# infinity_mirror_revf.net
KiCad netlist of a schematic drawn in EAGLE
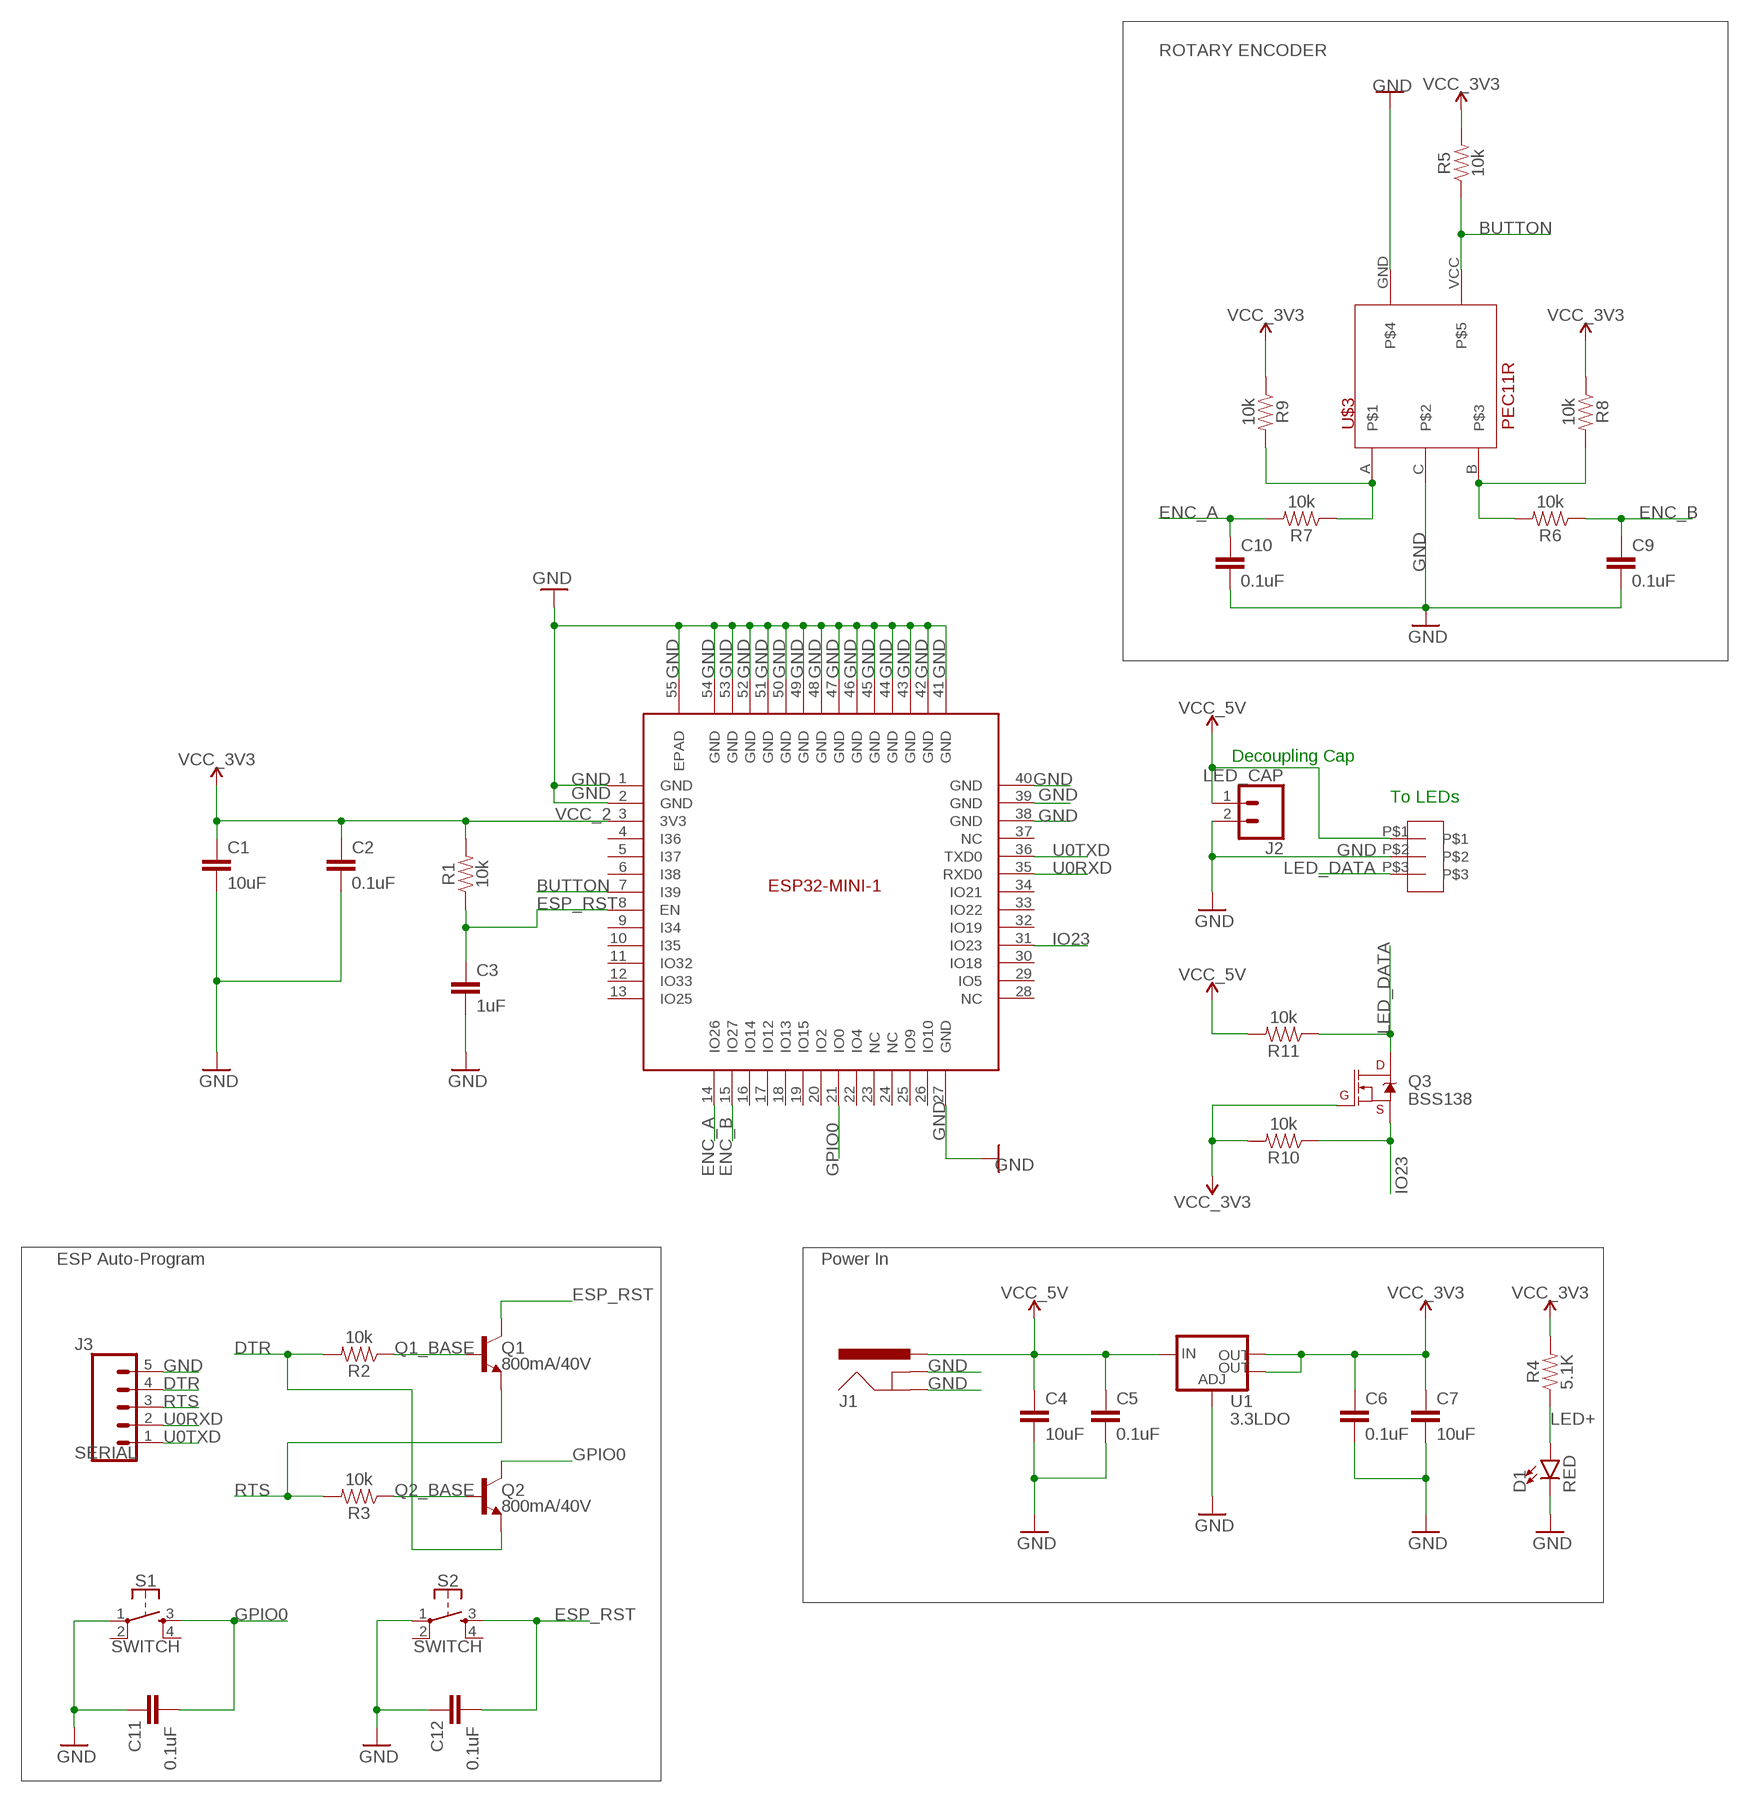
[diagram p0: schematic, sheet 1]

(export (version "E")
  (design (tool "Eeschema 10.0.6"))
  (components
    (comp (ref "C1")
      (value "10uF")
      (footprint "eagle-import:0805")
      (libsource (lib "eagle-import") (part "CAPACITOR"))
    )
    (comp (ref "C2")
      (value "0.1uF")
      (footprint "eagle-import:0805")
      (libsource (lib "eagle-import") (part "CAPACITOR"))
    )
    (comp (ref "C3")
      (value "1uF")
      (footprint "eagle-import:0805")
      (libsource (lib "eagle-import") (part "CAPACITOR"))
    )
    (comp (ref "C4")
      (value "10uF")
      (footprint "eagle-import:0805")
      (libsource (lib "eagle-import") (part "CAPACITOR"))
    )
    (comp (ref "C5")
      (value "0.1uF")
      (footprint "eagle-import:0805")
      (libsource (lib "eagle-import") (part "CAPACITOR"))
    )
    (comp (ref "C6")
      (value "0.1uF")
      (footprint "eagle-import:0805")
      (libsource (lib "eagle-import") (part "CAPACITOR"))
    )
    (comp (ref "C7")
      (value "10uF")
      (footprint "eagle-import:0805")
      (libsource (lib "eagle-import") (part "CAPACITOR"))
    )
    (comp (ref "C9")
      (value "0.1uF")
      (footprint "eagle-import:0805")
      (libsource (lib "eagle-import") (part "CAPACITOR"))
    )
    (comp (ref "C10")
      (value "0.1uF")
      (footprint "eagle-import:0805")
      (libsource (lib "eagle-import") (part "CAPACITOR"))
    )
    (comp (ref "C11")
      (value "0.1uF")
      (footprint "eagle-import:0805")
      (libsource (lib "eagle-import") (part "CAPACITOR"))
    )
    (comp (ref "C12")
      (value "0.1uF")
      (footprint "eagle-import:0805")
      (libsource (lib "eagle-import") (part "CAPACITOR"))
    )
    (comp (ref "D1")
      (value "RED")
      (footprint "eagle-import:LED-1206")
      (libsource (lib "eagle-import") (part "LED-RED1206"))
    )
    (comp (ref "J1")
      (value "POWER_JACKPTH_BREAD")
      (footprint "eagle-import:POWER_JACK_PTH_BREAD")
      (libsource (lib "eagle-import") (part "POWER_JACKPTH_BREAD"))
    )
    (comp (ref "J2")
      (value "LED_CAP")
      (footprint "eagle-import:1X02")
      (libsource (lib "eagle-import") (part "CONN_02"))
    )
    (comp (ref "J3")
      (value "SERIAL")
      (footprint "eagle-import:1X05")
      (libsource (lib "eagle-import") (part "CONN_05"))
    )
    (comp (ref "Q1")
      (value "800mA/40V")
      (footprint "eagle-import:SOT23-3")
      (libsource (lib "eagle-import") (part "TRANS_NPN-MMBT2222AL"))
    )
    (comp (ref "Q2")
      (value "800mA/40V")
      (footprint "eagle-import:SOT23-3")
      (libsource (lib "eagle-import") (part "TRANS_NPN-MMBT2222AL"))
    )
    (comp (ref "Q3")
      (value "BSS138")
      (footprint "eagle-import:SOT23-3")
      (libsource (lib "eagle-import") (part "MOSFET-NCH-BSS138"))
    )
    (comp (ref "R1")
      (value "10k")
      (footprint "eagle-import:0805")
      (libsource (lib "eagle-import") (part "RESISTOR"))
    )
    (comp (ref "R2")
      (value "10k")
      (footprint "eagle-import:0805")
      (libsource (lib "eagle-import") (part "RESISTOR"))
    )
    (comp (ref "R3")
      (value "10k")
      (footprint "eagle-import:0805")
      (libsource (lib "eagle-import") (part "RESISTOR"))
    )
    (comp (ref "R4")
      (value "5.1K")
      (footprint "eagle-import:0805")
      (libsource (lib "eagle-import") (part "RESISTOR"))
    )
    (comp (ref "R5")
      (value "10k")
      (footprint "eagle-import:0805")
      (libsource (lib "eagle-import") (part "RESISTOR"))
    )
    (comp (ref "R6")
      (value "10k")
      (footprint "eagle-import:0805")
      (libsource (lib "eagle-import") (part "RESISTOR"))
    )
    (comp (ref "R7")
      (value "10k")
      (footprint "eagle-import:0805")
      (libsource (lib "eagle-import") (part "RESISTOR"))
    )
    (comp (ref "R8")
      (value "10k")
      (footprint "eagle-import:0805")
      (libsource (lib "eagle-import") (part "RESISTOR"))
    )
    (comp (ref "R9")
      (value "10k")
      (footprint "eagle-import:0805")
      (libsource (lib "eagle-import") (part "RESISTOR"))
    )
    (comp (ref "R10")
      (value "10k")
      (footprint "eagle-import:0805")
      (libsource (lib "eagle-import") (part "RESISTOR"))
    )
    (comp (ref "R11")
      (value "10k")
      (footprint "eagle-import:0805")
      (libsource (lib "eagle-import") (part "RESISTOR"))
    )
    (comp (ref "S1")
      (value "SWITCH")
      (footprint "eagle-import:TACTILE_SWITCH_SMD_5.2MM")
      (libsource (lib "eagle-import") (part "MOMENTARY-SWITCH-SPST-2-SMD-5.2MM-TALL"))
    )
    (comp (ref "S2")
      (value "SWITCH")
      (footprint "eagle-import:TACTILE_SWITCH_SMD_5.2MM")
      (libsource (lib "eagle-import") (part "MOMENTARY-SWITCH-SPST-2-SMD-5.2MM-TALL"))
    )
    (comp (ref "U$1")
      (value "ESP32-MINI-1-N4")
      (footprint "eagle-import:ESP32-MINI-1-N4")
      (libsource (lib "eagle-import") (part "ESP32-MINI-1-N4"))
    )
    (comp (ref "U$2")
      (value "3-PIN-JST")
      (footprint "eagle-import:3-PIN-JST")
      (libsource (lib "eagle-import") (part "3-PIN-JST"))
    )
    (comp (ref "U$3")
      (value "PEC11R")
      (footprint "eagle-import:PEC11R-4320F-S0012")
      (libsource (lib "eagle-import") (part "PEC11R_ROTARY_ENCODER"))
    )
    (comp (ref "U1")
      (value "3.3LDO")
      (footprint "eagle-import:SOT223")
      (libsource (lib "eagle-import") (part "V_REG_LM1117SOT223"))
    )
  )
  (nets
    (net (code "1") (name "/BUTTON") (class "Default")
      (node (ref "R5") (pin "1") (pinfunction "1_1") (pintype "passive"))
      (node (ref "U$1") (pin "7") (pinfunction "I39_7") (pintype "bidirectional"))
      (node (ref "U$3") (pin "VCC") (pinfunction "P$5_VCC") (pintype "bidirectional"))
    )
    (net (code "2") (name "/DTR") (class "Default")
      (node (ref "J3") (pin "4") (pinfunction "4_4") (pintype "passive"))
      (node (ref "Q2") (pin "2") (pinfunction "E_2") (pintype "passive"))
      (node (ref "R2") (pin "2") (pinfunction "2_2") (pintype "passive"))
    )
    (net (code "3") (name "/ENC_A") (class "Default")
      (node (ref "C10") (pin "1") (pinfunction "1_1") (pintype "passive"))
      (node (ref "R7") (pin "2") (pinfunction "2_2") (pintype "passive"))
      (node (ref "U$1") (pin "14") (pinfunction "IO26_14") (pintype "bidirectional"))
    )
    (net (code "4") (name "/ENC_B") (class "Default")
      (node (ref "C9") (pin "1") (pinfunction "1_1") (pintype "passive"))
      (node (ref "R6") (pin "1") (pinfunction "1_1") (pintype "passive"))
      (node (ref "U$1") (pin "15") (pinfunction "IO27_15") (pintype "bidirectional"))
    )
    (net (code "5") (name "/ESP_RST") (class "Default")
      (node (ref "C12") (pin "2") (pinfunction "2_2") (pintype "passive"))
      (node (ref "C3") (pin "1") (pinfunction "1_1") (pintype "passive"))
      (node (ref "Q1") (pin "3") (pinfunction "C_3") (pintype "passive"))
      (node (ref "R1") (pin "1") (pinfunction "1_1") (pintype "passive"))
      (node (ref "S2") (pin "3") (pinfunction "3_3") (pintype "passive"))
      (node (ref "U$1") (pin "8") (pinfunction "EN_8") (pintype "bidirectional"))
    )
    (net (code "6") (name "/GPIO0") (class "Default")
      (node (ref "C11") (pin "2") (pinfunction "2_2") (pintype "passive"))
      (node (ref "Q2") (pin "3") (pinfunction "C_3") (pintype "passive"))
      (node (ref "S1") (pin "3") (pinfunction "3_3") (pintype "passive"))
      (node (ref "U$1") (pin "21") (pinfunction "IO0_21") (pintype "bidirectional"))
    )
    (net (code "7") (name "/IO23") (class "Default")
      (node (ref "Q3") (pin "2") (pinfunction "S_2") (pintype "bidirectional"))
      (node (ref "R10") (pin "1") (pinfunction "1_1") (pintype "passive"))
      (node (ref "U$1") (pin "31") (pinfunction "IO23_31") (pintype "bidirectional"))
    )
    (net (code "8") (name "/LED+") (class "Default")
      (node (ref "D1") (pin "A") (pinfunction "A_A") (pintype "passive"))
      (node (ref "R4") (pin "1") (pinfunction "1_1") (pintype "passive"))
    )
    (net (code "9") (name "/LED_DATA") (class "Default")
      (node (ref "Q3") (pin "3") (pinfunction "D_3") (pintype "bidirectional"))
      (node (ref "R11") (pin "1") (pinfunction "1_1") (pintype "passive"))
      (node (ref "U$2") (pin "P$3") (pinfunction "P$3_P$3") (pintype "bidirectional"))
    )
    (net (code "10") (name "/Q1_BASE") (class "Default")
      (node (ref "Q1") (pin "1") (pinfunction "B_1") (pintype "passive"))
      (node (ref "R2") (pin "1") (pinfunction "1_1") (pintype "passive"))
    )
    (net (code "11") (name "/Q2_BASE") (class "Default")
      (node (ref "Q2") (pin "1") (pinfunction "B_1") (pintype "passive"))
      (node (ref "R3") (pin "1") (pinfunction "1_1") (pintype "passive"))
    )
    (net (code "12") (name "/RTS") (class "Default")
      (node (ref "J3") (pin "3") (pinfunction "3_3") (pintype "passive"))
      (node (ref "Q1") (pin "2") (pinfunction "E_2") (pintype "passive"))
      (node (ref "R3") (pin "2") (pinfunction "2_2") (pintype "passive"))
    )
    (net (code "13") (name "/U0RXD") (class "Default")
      (node (ref "J3") (pin "2") (pinfunction "2_2") (pintype "passive"))
      (node (ref "U$1") (pin "35") (pinfunction "RXD0_35") (pintype "bidirectional"))
    )
    (net (code "14") (name "/U0TXD") (class "Default")
      (node (ref "J3") (pin "1") (pinfunction "1_1") (pintype "passive"))
      (node (ref "U$1") (pin "36") (pinfunction "TXD0_36") (pintype "bidirectional"))
    )
    (net (code "15") (name "GND") (class "Default")
      (node (ref "C1") (pin "2") (pinfunction "2_2") (pintype "passive"))
      (node (ref "C10") (pin "2") (pinfunction "2_2") (pintype "passive"))
      (node (ref "C11") (pin "1") (pinfunction "1_1") (pintype "passive"))
      (node (ref "C12") (pin "1") (pinfunction "1_1") (pintype "passive"))
      (node (ref "C2") (pin "2") (pinfunction "2_2") (pintype "passive"))
      (node (ref "C3") (pin "2") (pinfunction "2_2") (pintype "passive"))
      (node (ref "C4") (pin "2") (pinfunction "2_2") (pintype "passive"))
      (node (ref "C5") (pin "2") (pinfunction "2_2") (pintype "passive"))
      (node (ref "C6") (pin "2") (pinfunction "2_2") (pintype "passive"))
      (node (ref "C7") (pin "2") (pinfunction "2_2") (pintype "passive"))
      (node (ref "C9") (pin "2") (pinfunction "2_2") (pintype "passive"))
      (node (ref "D1") (pin "C") (pinfunction "C_C") (pintype "passive"))
      (node (ref "J1") (pin "GND") (pinfunction "GND_GND") (pintype "bidirectional"))
      (node (ref "J1") (pin "GNDBREAK") (pinfunction "GNDBREAK_GNDBREAK") (pintype "bidirectional"))
      (node (ref "J2") (pin "2") (pinfunction "2_2") (pintype "passive"))
      (node (ref "J3") (pin "5") (pinfunction "5_5") (pintype "passive"))
      (node (ref "S1") (pin "1") (pinfunction "1_1") (pintype "passive"))
      (node (ref "S2") (pin "1") (pinfunction "1_1") (pintype "passive"))
      (node (ref "U$1") (pin "1") (pinfunction "GND_1") (pintype "bidirectional"))
      (node (ref "U$1") (pin "2") (pinfunction "GND_2") (pintype "bidirectional"))
      (node (ref "U$1") (pin "27") (pinfunction "GND_27") (pintype "bidirectional"))
      (node (ref "U$1") (pin "38") (pinfunction "GND_38") (pintype "bidirectional"))
      (node (ref "U$1") (pin "39") (pinfunction "GND_39") (pintype "bidirectional"))
      (node (ref "U$1") (pin "40") (pinfunction "GND_40") (pintype "bidirectional"))
      (node (ref "U$1") (pin "41") (pinfunction "GND_41") (pintype "bidirectional"))
      (node (ref "U$1") (pin "42") (pinfunction "GND_42") (pintype "bidirectional"))
      (node (ref "U$1") (pin "43") (pinfunction "GND_43") (pintype "bidirectional"))
      (node (ref "U$1") (pin "44") (pinfunction "GND_44") (pintype "bidirectional"))
      (node (ref "U$1") (pin "45") (pinfunction "GND_45") (pintype "bidirectional"))
      (node (ref "U$1") (pin "46") (pinfunction "GND_46") (pintype "bidirectional"))
      (node (ref "U$1") (pin "47") (pinfunction "GND_47") (pintype "bidirectional"))
      (node (ref "U$1") (pin "48") (pinfunction "GND_48") (pintype "bidirectional"))
      (node (ref "U$1") (pin "49") (pinfunction "GND_49") (pintype "bidirectional"))
      (node (ref "U$1") (pin "50") (pinfunction "GND_50") (pintype "bidirectional"))
      (node (ref "U$1") (pin "51") (pinfunction "GND_51") (pintype "bidirectional"))
      (node (ref "U$1") (pin "52") (pinfunction "GND_52") (pintype "bidirectional"))
      (node (ref "U$1") (pin "53") (pinfunction "GND_53") (pintype "bidirectional"))
      (node (ref "U$1") (pin "54") (pinfunction "GND_54") (pintype "bidirectional"))
      (node (ref "U$1") (pin "55") (pinfunction "EPAD_55") (pintype "bidirectional"))
      (node (ref "U$2") (pin "P$2") (pinfunction "P$2_P$2") (pintype "bidirectional"))
      (node (ref "U$3") (pin "C") (pinfunction "P$2_C") (pintype "bidirectional"))
      (node (ref "U$3") (pin "GND") (pinfunction "P$4_GND") (pintype "bidirectional"))
      (node (ref "U1") (pin "1") (pinfunction "ADJ_1") (pintype "input"))
    )
    (net (code "16") (name "Net-(U$3-P$1)") (class "Default")
      (node (ref "R7") (pin "1") (pinfunction "1_1") (pintype "passive"))
      (node (ref "R9") (pin "2") (pinfunction "2_2") (pintype "passive"))
      (node (ref "U$3") (pin "A") (pinfunction "P$1_A") (pintype "bidirectional"))
    )
    (net (code "17") (name "Net-(U$3-P$3)") (class "Default")
      (node (ref "R6") (pin "2") (pinfunction "2_2") (pintype "passive"))
      (node (ref "R8") (pin "2") (pinfunction "2_2") (pintype "passive"))
      (node (ref "U$3") (pin "B") (pinfunction "P$3_B") (pintype "bidirectional"))
    )
    (net (code "18") (name "VCC_3V3") (class "Default")
      (node (ref "C1") (pin "1") (pinfunction "1_1") (pintype "passive"))
      (node (ref "C2") (pin "1") (pinfunction "1_1") (pintype "passive"))
      (node (ref "C6") (pin "1") (pinfunction "1_1") (pintype "passive"))
      (node (ref "C7") (pin "1") (pinfunction "1_1") (pintype "passive"))
      (node (ref "Q3") (pin "1") (pinfunction "G_1") (pintype "bidirectional"))
      (node (ref "R1") (pin "2") (pinfunction "2_2") (pintype "passive"))
      (node (ref "R10") (pin "2") (pinfunction "2_2") (pintype "passive"))
      (node (ref "R4") (pin "2") (pinfunction "2_2") (pintype "passive"))
      (node (ref "R5") (pin "2") (pinfunction "2_2") (pintype "passive"))
      (node (ref "R8") (pin "1") (pinfunction "1_1") (pintype "passive"))
      (node (ref "R9") (pin "1") (pinfunction "1_1") (pintype "passive"))
      (node (ref "U$1") (pin "3") (pinfunction "3V3_3") (pintype "bidirectional"))
      (node (ref "U1") (pin "2") (pinfunction "OUT_2") (pintype "output"))
      (node (ref "U1") (pin "4") (pinfunction "OUT_4") (pintype "output"))
    )
    (net (code "19") (name "VCC_5V") (class "Default")
      (node (ref "C4") (pin "1") (pinfunction "1_1") (pintype "passive"))
      (node (ref "C5") (pin "1") (pinfunction "1_1") (pintype "passive"))
      (node (ref "J1") (pin "PWR") (pinfunction "PWR_PWR") (pintype "bidirectional"))
      (node (ref "J2") (pin "1") (pinfunction "1_1") (pintype "passive"))
      (node (ref "R11") (pin "2") (pinfunction "2_2") (pintype "passive"))
      (node (ref "U$2") (pin "P$1") (pinfunction "P$1_P$1") (pintype "bidirectional"))
      (node (ref "U1") (pin "3") (pinfunction "IN_3") (pintype "input"))
    )
    (net (code "20") (name "unconnected-(S1-Pad2)") (class "Default")
      (node (ref "S1") (pin "2") (pinfunction "2_2") (pintype "passive"))
    )
    (net (code "21") (name "unconnected-(S1-Pad4)") (class "Default")
      (node (ref "S1") (pin "4") (pinfunction "4_4") (pintype "passive"))
    )
    (net (code "22") (name "unconnected-(S2-Pad2)") (class "Default")
      (node (ref "S2") (pin "2") (pinfunction "2_2") (pintype "passive"))
    )
    (net (code "23") (name "unconnected-(S2-Pad4)") (class "Default")
      (node (ref "S2") (pin "4") (pinfunction "4_4") (pintype "passive"))
    )
    (net (code "24") (name "unconnected-(U$1-I34-Pad9)") (class "Default")
      (node (ref "U$1") (pin "9") (pinfunction "I34_9") (pintype "bidirectional"))
    )
    (net (code "25") (name "unconnected-(U$1-I35-Pad10)") (class "Default")
      (node (ref "U$1") (pin "10") (pinfunction "I35_10") (pintype "bidirectional"))
    )
    (net (code "26") (name "unconnected-(U$1-I36-Pad4)") (class "Default")
      (node (ref "U$1") (pin "4") (pinfunction "I36_4") (pintype "bidirectional"))
    )
    (net (code "27") (name "unconnected-(U$1-I37-Pad5)") (class "Default")
      (node (ref "U$1") (pin "5") (pinfunction "I37_5") (pintype "bidirectional"))
    )
    (net (code "28") (name "unconnected-(U$1-I38-Pad6)") (class "Default")
      (node (ref "U$1") (pin "6") (pinfunction "I38_6") (pintype "bidirectional"))
    )
    (net (code "29") (name "unconnected-(U$1-IO2-Pad20)") (class "Default")
      (node (ref "U$1") (pin "20") (pinfunction "IO2_20") (pintype "bidirectional"))
    )
    (net (code "30") (name "unconnected-(U$1-IO4-Pad22)") (class "Default")
      (node (ref "U$1") (pin "22") (pinfunction "IO4_22") (pintype "bidirectional"))
    )
    (net (code "31") (name "unconnected-(U$1-IO5-Pad29)") (class "Default")
      (node (ref "U$1") (pin "29") (pinfunction "IO5_29") (pintype "bidirectional"))
    )
    (net (code "32") (name "unconnected-(U$1-IO9-Pad25)") (class "Default")
      (node (ref "U$1") (pin "25") (pinfunction "IO9_25") (pintype "bidirectional"))
    )
    (net (code "33") (name "unconnected-(U$1-IO10-Pad26)") (class "Default")
      (node (ref "U$1") (pin "26") (pinfunction "IO10_26") (pintype "bidirectional"))
    )
    (net (code "34") (name "unconnected-(U$1-IO12-Pad17)") (class "Default")
      (node (ref "U$1") (pin "17") (pinfunction "IO12_17") (pintype "bidirectional"))
    )
    (net (code "35") (name "unconnected-(U$1-IO13-Pad18)") (class "Default")
      (node (ref "U$1") (pin "18") (pinfunction "IO13_18") (pintype "bidirectional"))
    )
    (net (code "36") (name "unconnected-(U$1-IO14-Pad16)") (class "Default")
      (node (ref "U$1") (pin "16") (pinfunction "IO14_16") (pintype "bidirectional"))
    )
    (net (code "37") (name "unconnected-(U$1-IO15-Pad19)") (class "Default")
      (node (ref "U$1") (pin "19") (pinfunction "IO15_19") (pintype "bidirectional"))
    )
    (net (code "38") (name "unconnected-(U$1-IO18-Pad30)") (class "Default")
      (node (ref "U$1") (pin "30") (pinfunction "IO18_30") (pintype "bidirectional"))
    )
    (net (code "39") (name "unconnected-(U$1-IO19-Pad32)") (class "Default")
      (node (ref "U$1") (pin "32") (pinfunction "IO19_32") (pintype "bidirectional"))
    )
    (net (code "40") (name "unconnected-(U$1-IO21-Pad34)") (class "Default")
      (node (ref "U$1") (pin "34") (pinfunction "IO21_34") (pintype "bidirectional"))
    )
    (net (code "41") (name "unconnected-(U$1-IO22-Pad33)") (class "Default")
      (node (ref "U$1") (pin "33") (pinfunction "IO22_33") (pintype "bidirectional"))
    )
    (net (code "42") (name "unconnected-(U$1-IO25-Pad13)") (class "Default")
      (node (ref "U$1") (pin "13") (pinfunction "IO25_13") (pintype "bidirectional"))
    )
    (net (code "43") (name "unconnected-(U$1-IO32-Pad11)") (class "Default")
      (node (ref "U$1") (pin "11") (pinfunction "IO32_11") (pintype "bidirectional"))
    )
    (net (code "44") (name "unconnected-(U$1-IO33-Pad12)") (class "Default")
      (node (ref "U$1") (pin "12") (pinfunction "IO33_12") (pintype "bidirectional"))
    )
    (net (code "45") (name "unconnected-(U$1-NC-Pad23)") (class "Default")
      (node (ref "U$1") (pin "23") (pinfunction "NC_23") (pintype "bidirectional"))
    )
    (net (code "46") (name "unconnected-(U$1-NC-Pad24)") (class "Default")
      (node (ref "U$1") (pin "24") (pinfunction "NC_24") (pintype "bidirectional"))
    )
    (net (code "47") (name "unconnected-(U$1-NC-Pad28)") (class "Default")
      (node (ref "U$1") (pin "28") (pinfunction "NC_28") (pintype "bidirectional"))
    )
    (net (code "48") (name "unconnected-(U$1-NC-Pad37)") (class "Default")
      (node (ref "U$1") (pin "37") (pinfunction "NC_37") (pintype "bidirectional"))
    )
  )
)
